# SB_TS_2_08_Final.net
KiCad netlist of a schematic drawn in EAGLE
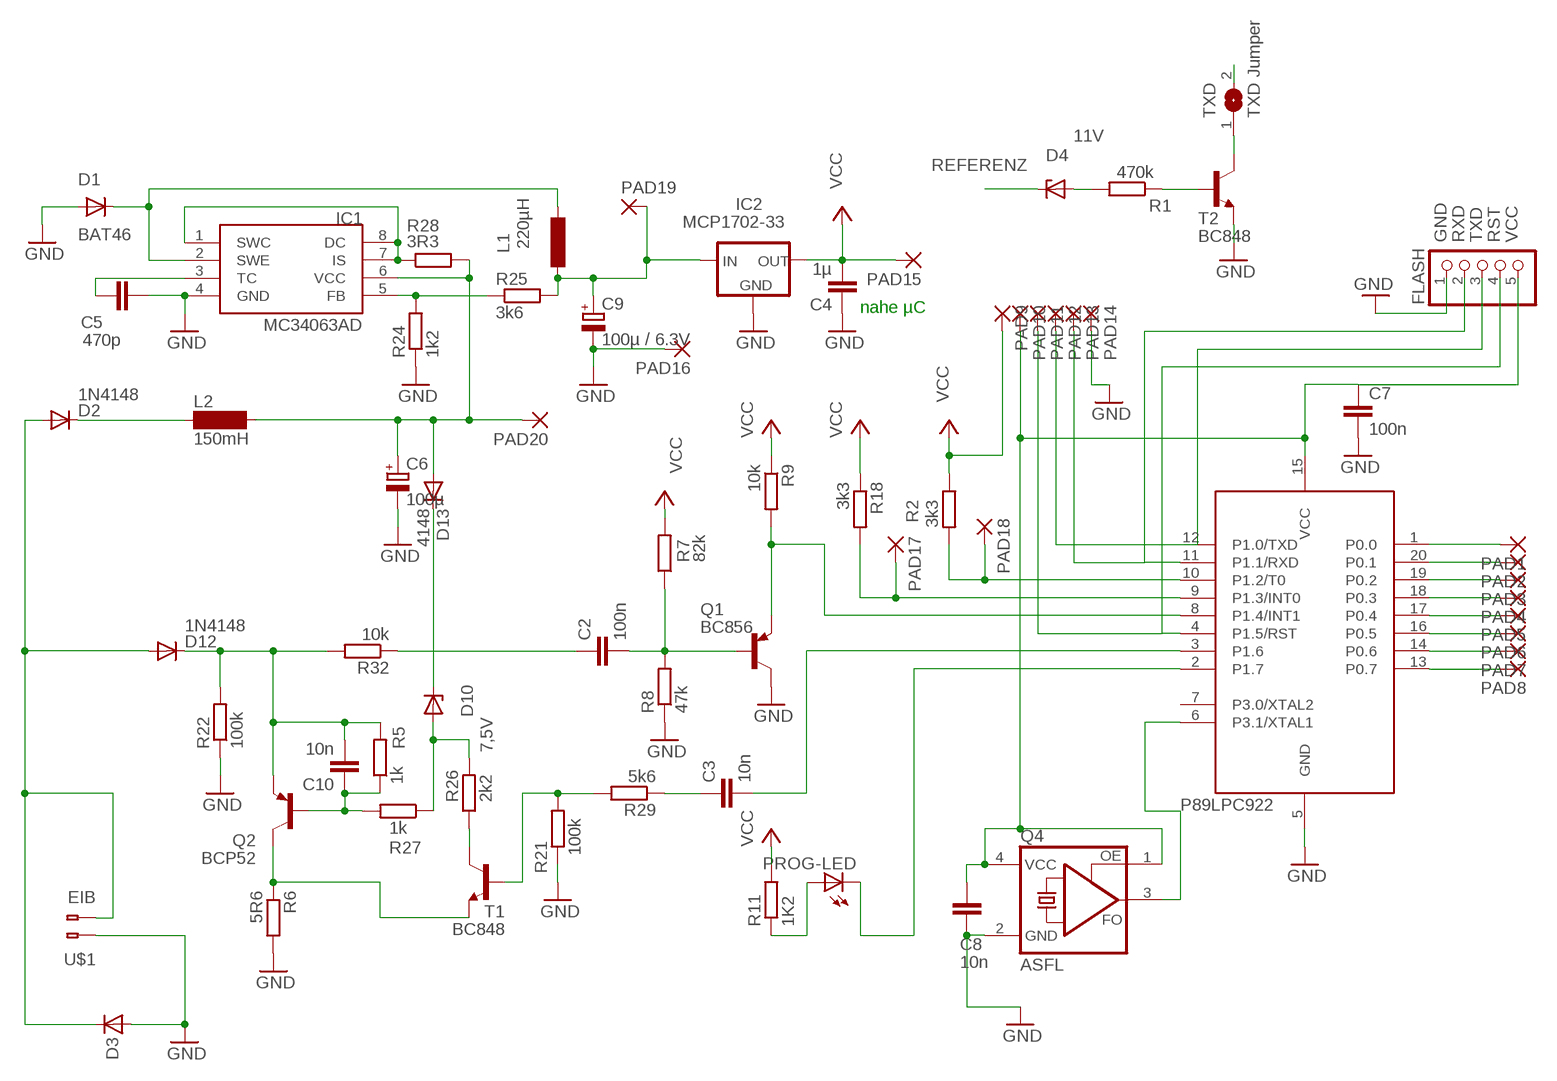
[diagram p0: schematic, sheet 1]

(export (version "E")
  (design (tool "Eeschema 10.0.6"))
  (components
    (comp (ref "C2")
      (value "100n")
      (footprint "eagle-import:C1206")
      (libsource (lib "eagle-import") (part "C-EUC1206"))
    )
    (comp (ref "C3")
      (value "10n")
      (footprint "eagle-import:C1206")
      (libsource (lib "eagle-import") (part "C-EUC1206"))
    )
    (comp (ref "C4")
      (value "1µ")
      (footprint "eagle-import:C1206")
      (libsource (lib "eagle-import") (part "C-EUC1206"))
    )
    (comp (ref "C5")
      (value "470p")
      (footprint "eagle-import:C1206")
      (libsource (lib "eagle-import") (part "C-EUC1206"))
    )
    (comp (ref "C6")
      (value "100µ")
      (footprint "eagle-import:SANYO-OSCON_SMD_C6")
      (libsource (lib "eagle-import") (part "CPOL-EUSANYO_SMD_C6"))
    )
    (comp (ref "C7")
      (value "100n")
      (footprint "eagle-import:C1206")
      (libsource (lib "eagle-import") (part "C-EUC1206"))
    )
    (comp (ref "C8")
      (value "10n")
      (footprint "eagle-import:C1206")
      (libsource (lib "eagle-import") (part "C-EUC1206"))
    )
    (comp (ref "C9")
      (value "100µ / 6.3V")
      (footprint "eagle-import:E2,5-5")
      (libsource (lib "eagle-import") (part "CPOL-EUE2.5-5"))
    )
    (comp (ref "C10")
      (value "10n")
      (footprint "eagle-import:C1206")
      (libsource (lib "eagle-import") (part "C-EUC1206"))
    )
    (comp (ref "D1")
      (value "BAT46")
      (footprint "eagle-import:MINIMELF")
      (libsource (lib "eagle-import") (part "DIODE-MINIMELF"))
    )
    (comp (ref "D2")
      (value "1N4148")
      (footprint "eagle-import:MINIMELF")
      (libsource (lib "eagle-import") (part "DIODE-MINIMELF"))
    )
    (comp (ref "D3")
      (value "SMAJ40AC")
      (footprint "eagle-import:SMB")
      (libsource (lib "eagle-import") (part "D-SMB"))
    )
    (comp (ref "D4")
      (value "11V")
      (footprint "eagle-import:SOD80C")
      (libsource (lib "eagle-import") (part "ZENER-DIODESOD80C"))
    )
    (comp (ref "D10")
      (value "7,5V")
      (footprint "eagle-import:SOD80C")
      (libsource (lib "eagle-import") (part "ZENER-DIODESOD80C"))
    )
    (comp (ref "D12")
      (value "1N4148")
      (footprint "eagle-import:MINIMELF")
      (libsource (lib "eagle-import") (part "DIODE-MINIMELF"))
    )
    (comp (ref "D13")
      (value "4148")
      (footprint "eagle-import:MINIMELF")
      (libsource (lib "eagle-import") (part "DIODE-MINIMELF"))
    )
    (comp (ref "FLASH")
      (value "PINHD-1X5")
      (footprint "eagle-import:1X05")
      (libsource (lib "eagle-import") (part "PINHD-1X5"))
    )
    (comp (ref "IC1")
      (value "MC34063AD")
      (footprint "eagle-import:SOIC8")
      (libsource (lib "eagle-import") (part "MC34063AD"))
    )
    (comp (ref "IC2")
      (value "MCP1702-33")
      (footprint "eagle-import:79LXX")
      (libsource (lib "eagle-import") (part "79LXX"))
    )
    (comp (ref "IC3")
      (value "LPC922FDH")
      (footprint "eagle-import:TSSOP20")
      (libsource (lib "eagle-import") (part "LPC922FDH"))
    )
    (comp (ref "L1")
      (value "220µH")
      (footprint "eagle-import:2200-11.43")
      (libsource (lib "eagle-import") (part "L-EU2200-11.43"))
    )
    (comp (ref "L2")
      (value "150mH")
      (footprint "eagle-import:SD12_1000")
      (libsource (lib "eagle-import") (part "SD12-1000"))
    )
    (comp (ref "PAD1")
      (value "SMD2")
      (footprint "eagle-import:SMD1,27-2,54")
      (libsource (lib "eagle-import") (part "SMD2"))
    )
    (comp (ref "PAD2")
      (value "SMD2")
      (footprint "eagle-import:SMD1,27-2,54")
      (libsource (lib "eagle-import") (part "SMD2"))
    )
    (comp (ref "PAD3")
      (value "SMD2")
      (footprint "eagle-import:SMD1,27-2,54")
      (libsource (lib "eagle-import") (part "SMD2"))
    )
    (comp (ref "PAD4")
      (value "SMD2")
      (footprint "eagle-import:SMD1,27-2,54")
      (libsource (lib "eagle-import") (part "SMD2"))
    )
    (comp (ref "PAD5")
      (value "SMD2")
      (footprint "eagle-import:SMD1,27-2,54")
      (libsource (lib "eagle-import") (part "SMD2"))
    )
    (comp (ref "PAD6")
      (value "SMD2")
      (footprint "eagle-import:SMD1,27-2,54")
      (libsource (lib "eagle-import") (part "SMD2"))
    )
    (comp (ref "PAD7")
      (value "SMD2")
      (footprint "eagle-import:SMD1,27-2,54")
      (libsource (lib "eagle-import") (part "SMD2"))
    )
    (comp (ref "PAD8")
      (value "SMD2")
      (footprint "eagle-import:SMD1,27-2,54")
      (libsource (lib "eagle-import") (part "SMD2"))
    )
    (comp (ref "PAD9")
      (value "SMD2")
      (footprint "eagle-import:SMD1,27-2,54")
      (libsource (lib "eagle-import") (part "SMD2"))
    )
    (comp (ref "PAD10")
      (value "SMD2")
      (footprint "eagle-import:SMD1,27-2,54")
      (libsource (lib "eagle-import") (part "SMD2"))
    )
    (comp (ref "PAD11")
      (value "SMD2")
      (footprint "eagle-import:SMD1,27-2,54")
      (libsource (lib "eagle-import") (part "SMD2"))
    )
    (comp (ref "PAD12")
      (value "SMD2")
      (footprint "eagle-import:SMD1,27-2,54")
      (libsource (lib "eagle-import") (part "SMD2"))
    )
    (comp (ref "PAD13")
      (value "SMD2")
      (footprint "eagle-import:SMD1,27-2,54")
      (libsource (lib "eagle-import") (part "SMD2"))
    )
    (comp (ref "PAD14")
      (value "SMD2")
      (footprint "eagle-import:SMD1,27-2,54")
      (libsource (lib "eagle-import") (part "SMD2"))
    )
    (comp (ref "PAD15")
      (value "SMD2")
      (footprint "eagle-import:SMD1,27-2,54")
      (libsource (lib "eagle-import") (part "SMD2"))
    )
    (comp (ref "PAD16")
      (value "SMD2")
      (footprint "eagle-import:SMD1,27-2,54")
      (libsource (lib "eagle-import") (part "SMD2"))
    )
    (comp (ref "PAD17")
      (value "SMD2")
      (footprint "eagle-import:SMD1,27-2,54")
      (libsource (lib "eagle-import") (part "SMD2"))
    )
    (comp (ref "PAD18")
      (value "SMD2")
      (footprint "eagle-import:SMD1,27-2,54")
      (libsource (lib "eagle-import") (part "SMD2"))
    )
    (comp (ref "PAD19")
      (value "SMD2")
      (footprint "eagle-import:SMD1,27-2,54")
      (libsource (lib "eagle-import") (part "SMD2"))
    )
    (comp (ref "PAD20")
      (value "SMD2")
      (footprint "eagle-import:SMD1,27-2,54")
      (libsource (lib "eagle-import") (part "SMD2"))
    )
    (comp (ref "PROG-LED")
      (value "LEDCHIPLED_1206")
      (footprint "eagle-import:CHIPLED_1206")
      (libsource (lib "eagle-import") (part "LEDCHIPLED_1206"))
    )
    (comp (ref "Q1")
      (value "BC856")
      (footprint "eagle-import:SOT23-BEC")
      (libsource (lib "eagle-import") (part "BC856SMDALT1"))
    )
    (comp (ref "Q2")
      (value "BCP52")
      (footprint "eagle-import:SOT223")
      (libsource (lib "eagle-import") (part "FZT753SMD"))
    )
    (comp (ref "Q4")
      (value "ASFL")
      (footprint "eagle-import:ASF")
      (fields (field (name "MPN") "ASFLM1-50.000MHZ-C-T"))
      (libsource (lib "eagle-import") (part "ASFL"))
    )
    (comp (ref "R1")
      (value "470k")
      (footprint "eagle-import:R1206")
      (libsource (lib "eagle-import") (part "R-EU_R1206"))
    )
    (comp (ref "R2")
      (value "3k3")
      (footprint "eagle-import:M1206")
      (libsource (lib "eagle-import") (part "R-EU_M1206"))
    )
    (comp (ref "R5")
      (value "1k")
      (footprint "eagle-import:R1206")
      (libsource (lib "eagle-import") (part "R-EU_R1206"))
    )
    (comp (ref "R6")
      (value "5R6")
      (footprint "eagle-import:R1206")
      (libsource (lib "eagle-import") (part "R-EU_R1206"))
    )
    (comp (ref "R7")
      (value "82k")
      (footprint "eagle-import:R1206")
      (libsource (lib "eagle-import") (part "R-EU_R1206"))
    )
    (comp (ref "R8")
      (value "47k")
      (footprint "eagle-import:M1206")
      (libsource (lib "eagle-import") (part "R-EU_M1206"))
    )
    (comp (ref "R9")
      (value "10k")
      (footprint "eagle-import:R1206")
      (libsource (lib "eagle-import") (part "R-EU_R1206"))
    )
    (comp (ref "R11")
      (value "1K2")
      (footprint "eagle-import:R1206")
      (libsource (lib "eagle-import") (part "R-EU_R1206"))
    )
    (comp (ref "R18")
      (value "3k3")
      (footprint "eagle-import:R1206")
      (libsource (lib "eagle-import") (part "R-EU_R1206"))
    )
    (comp (ref "R21")
      (value "100k")
      (footprint "eagle-import:R1206")
      (libsource (lib "eagle-import") (part "R-EU_R1206"))
    )
    (comp (ref "R22")
      (value "100k")
      (footprint "eagle-import:M1206")
      (libsource (lib "eagle-import") (part "R-EU_M1206"))
    )
    (comp (ref "R24")
      (value "1k2")
      (footprint "eagle-import:R1206")
      (libsource (lib "eagle-import") (part "R-EU_R1206"))
    )
    (comp (ref "R25")
      (value "3k6")
      (footprint "eagle-import:M1206")
      (libsource (lib "eagle-import") (part "R-EU_M1206"))
    )
    (comp (ref "R26")
      (value "2k2")
      (footprint "eagle-import:M1206")
      (libsource (lib "eagle-import") (part "R-EU_M1206"))
    )
    (comp (ref "R27")
      (value "1k")
      (footprint "eagle-import:R1206")
      (libsource (lib "eagle-import") (part "R-EU_R1206"))
    )
    (comp (ref "R28")
      (value "3R3")
      (footprint "eagle-import:M1206")
      (libsource (lib "eagle-import") (part "R-EU_M1206"))
    )
    (comp (ref "R29")
      (value "5k6")
      (footprint "eagle-import:R1206")
      (libsource (lib "eagle-import") (part "R-EU_R1206"))
    )
    (comp (ref "R32")
      (value "10k")
      (footprint "eagle-import:R1206")
      (libsource (lib "eagle-import") (part "R-EU_R1206"))
    )
    (comp (ref "T1")
      (value "BC848")
      (footprint "eagle-import:SOT23")
      (libsource (lib "eagle-import") (part "BC848"))
    )
    (comp (ref "T2")
      (value "BC848")
      (footprint "eagle-import:SOT23")
      (libsource (lib "eagle-import") (part "BC848"))
    )
    (comp (ref "TXD")
      (value "TXD Jumper")
      (footprint "eagle-import:SJ")
      (libsource (lib "eagle-import") (part "SJ"))
    )
    (comp (ref "U$1")
      (value "EIB")
      (footprint "eagle-import:BUSKLEMME243-724")
      (libsource (lib "eagle-import") (part "EIB"))
    )
  )
  (nets
    (net (code "1") (name "/REFERENZ") (class "Default")
      (node (ref "D10") (pin "A") (pinfunction "A_A") (pintype "passive"))
      (node (ref "D4") (pin "C") (pinfunction "C_C") (pintype "passive"))
      (node (ref "R26") (pin "2") (pinfunction "2_2") (pintype "passive"))
      (node (ref "R27") (pin "1") (pinfunction "1_1") (pintype "passive"))
    )
    (net (code "2") (name "/TXD") (class "Default")
      (node (ref "FLASH") (pin "3") (pinfunction "3_3") (pintype "passive"))
      (node (ref "IC3") (pin "12") (pinfunction "P1.0/TXD_12") (pintype "bidirectional"))
      (node (ref "PAD12") (pin "1") (pinfunction "P_1") (pintype "passive"))
      (node (ref "T2") (pin "3") (pinfunction "C_3") (pintype "passive"))
      (node (ref "TXD") (pin "1") (pinfunction "1_1") (pintype "passive"))
      (node (ref "TXD") (pin "2") (pinfunction "2_2") (pintype "passive"))
    )
    (net (code "3") (name "GND") (class "Default")
      (node (ref "C4") (pin "1") (pinfunction "1_1") (pintype "passive"))
      (node (ref "C5") (pin "2") (pinfunction "2_2") (pintype "passive"))
      (node (ref "C6") (pin "-") (pinfunction "-_-") (pintype "passive"))
      (node (ref "C7") (pin "2") (pinfunction "2_2") (pintype "passive"))
      (node (ref "C8") (pin "2") (pinfunction "2_2") (pintype "passive"))
      (node (ref "C9") (pin "-") (pinfunction "-_-") (pintype "passive"))
      (node (ref "D1") (pin "A") (pinfunction "A_A") (pintype "passive"))
      (node (ref "D3") (pin "2") (pinfunction "A_2") (pintype "passive"))
      (node (ref "FLASH") (pin "1") (pinfunction "1_1") (pintype "passive"))
      (node (ref "IC1") (pin "4") (pinfunction "GND_4") (pintype "passive"))
      (node (ref "IC2") (pin "GND") (pinfunction "GND_GND") (pintype "input"))
      (node (ref "IC3") (pin "5") (pinfunction "GND_5") (pintype "bidirectional"))
      (node (ref "PAD14") (pin "1") (pinfunction "P_1") (pintype "passive"))
      (node (ref "PAD16") (pin "1") (pinfunction "P_1") (pintype "passive"))
      (node (ref "Q1") (pin "C") (pinfunction "C_C") (pintype "passive"))
      (node (ref "Q4") (pin "2") (pinfunction "GND_2") (pintype "power_in"))
      (node (ref "R21") (pin "1") (pinfunction "1_1") (pintype "passive"))
      (node (ref "R22") (pin "1") (pinfunction "1_1") (pintype "passive"))
      (node (ref "R24") (pin "1") (pinfunction "1_1") (pintype "passive"))
      (node (ref "R6") (pin "2") (pinfunction "2_2") (pintype "passive"))
      (node (ref "R8") (pin "1") (pinfunction "1_1") (pintype "passive"))
      (node (ref "T2") (pin "2") (pinfunction "E_2") (pintype "passive"))
      (node (ref "U$1") (pin "1") (pinfunction "B-1_1") (pintype "passive"))
    )
    (net (code "4") (name "Net-(C2-Pad1)") (class "Default")
      (node (ref "C2") (pin "1") (pinfunction "1_1") (pintype "passive"))
      (node (ref "R32") (pin "1") (pinfunction "1_1") (pintype "passive"))
    )
    (net (code "5") (name "Net-(C2-Pad2)") (class "Default")
      (node (ref "C2") (pin "2") (pinfunction "2_2") (pintype "passive"))
      (node (ref "Q1") (pin "B") (pinfunction "B_B") (pintype "passive"))
      (node (ref "R7") (pin "1") (pinfunction "1_1") (pintype "passive"))
      (node (ref "R8") (pin "2") (pinfunction "2_2") (pintype "passive"))
    )
    (net (code "6") (name "Net-(C3-Pad1)") (class "Default")
      (node (ref "C3") (pin "1") (pinfunction "1_1") (pintype "passive"))
      (node (ref "R29") (pin "1") (pinfunction "1_1") (pintype "passive"))
    )
    (net (code "7") (name "Net-(D2-PadC)") (class "Default")
      (node (ref "D2") (pin "C") (pinfunction "C_C") (pintype "passive"))
      (node (ref "L2") (pin "1") (pinfunction "1_1") (pintype "passive"))
    )
    (net (code "8") (name "Net-(D3-C)") (class "Default")
      (node (ref "D12") (pin "A") (pinfunction "A_A") (pintype "passive"))
      (node (ref "D2") (pin "A") (pinfunction "A_A") (pintype "passive"))
      (node (ref "D3") (pin "1") (pinfunction "C_1") (pintype "passive"))
      (node (ref "U$1") (pin "2") (pinfunction "B-2_2") (pintype "passive"))
    )
    (net (code "9") (name "Net-(D4-PadA)") (class "Default")
      (node (ref "D4") (pin "A") (pinfunction "A_A") (pintype "passive"))
      (node (ref "R1") (pin "2") (pinfunction "2_2") (pintype "passive"))
    )
    (net (code "10") (name "Net-(D10-PadC)") (class "Default")
      (node (ref "D10") (pin "C") (pinfunction "C_C") (pintype "passive"))
      (node (ref "D13") (pin "C") (pinfunction "C_C") (pintype "passive"))
    )
    (net (code "11") (name "Net-(IC1-DC)") (class "Default")
      (node (ref "IC1") (pin "1") (pinfunction "SWC_1") (pintype "passive"))
      (node (ref "IC1") (pin "7") (pinfunction "IS_7") (pintype "passive"))
      (node (ref "IC1") (pin "8") (pinfunction "DC_8") (pintype "passive"))
      (node (ref "R28") (pin "1") (pinfunction "1_1") (pintype "passive"))
    )
    (net (code "12") (name "Net-(IC1-FB)") (class "Default")
      (node (ref "IC1") (pin "5") (pinfunction "FB_5") (pintype "passive"))
      (node (ref "R24") (pin "2") (pinfunction "2_2") (pintype "passive"))
      (node (ref "R25") (pin "1") (pinfunction "1_1") (pintype "passive"))
    )
    (net (code "13") (name "Net-(IC1-SWE)") (class "Default")
      (node (ref "D1") (pin "C") (pinfunction "C_C") (pintype "passive"))
      (node (ref "IC1") (pin "2") (pinfunction "SWE_2") (pintype "passive"))
      (node (ref "L1") (pin "2") (pinfunction "2_2") (pintype "passive"))
    )
    (net (code "14") (name "Net-(IC1-TC)") (class "Default")
      (node (ref "C5") (pin "1") (pinfunction "1_1") (pintype "passive"))
      (node (ref "IC1") (pin "3") (pinfunction "TC_3") (pintype "passive"))
    )
    (net (code "15") (name "Net-(IC1-VCC)") (class "Default")
      (node (ref "C6") (pin "+") (pinfunction "+_+") (pintype "passive"))
      (node (ref "D13") (pin "A") (pinfunction "A_A") (pintype "passive"))
      (node (ref "IC1") (pin "6") (pinfunction "VCC_6") (pintype "passive"))
      (node (ref "L2") (pin "2") (pinfunction "2_2") (pintype "passive"))
      (node (ref "PAD20") (pin "1") (pinfunction "P_1") (pintype "passive"))
      (node (ref "R28") (pin "2") (pinfunction "2_2") (pintype "passive"))
    )
    (net (code "16") (name "Net-(IC3-P0.0)") (class "Default")
      (node (ref "IC3") (pin "1") (pinfunction "P0.0_1") (pintype "bidirectional"))
      (node (ref "PAD1") (pin "1") (pinfunction "P_1") (pintype "passive"))
    )
    (net (code "17") (name "Net-(IC3-P0.1)") (class "Default")
      (node (ref "IC3") (pin "20") (pinfunction "P0.1_20") (pintype "bidirectional"))
      (node (ref "PAD2") (pin "1") (pinfunction "P_1") (pintype "passive"))
    )
    (net (code "18") (name "Net-(IC3-P0.2)") (class "Default")
      (node (ref "IC3") (pin "19") (pinfunction "P0.2_19") (pintype "bidirectional"))
      (node (ref "PAD3") (pin "1") (pinfunction "P_1") (pintype "passive"))
    )
    (net (code "19") (name "Net-(IC3-P0.3)") (class "Default")
      (node (ref "IC3") (pin "18") (pinfunction "P0.3_18") (pintype "bidirectional"))
      (node (ref "PAD4") (pin "1") (pinfunction "P_1") (pintype "passive"))
    )
    (net (code "20") (name "Net-(IC3-P0.4)") (class "Default")
      (node (ref "IC3") (pin "17") (pinfunction "P0.4_17") (pintype "bidirectional"))
      (node (ref "PAD5") (pin "1") (pinfunction "P_1") (pintype "passive"))
    )
    (net (code "21") (name "Net-(IC3-P0.5)") (class "Default")
      (node (ref "IC3") (pin "16") (pinfunction "P0.5_16") (pintype "bidirectional"))
      (node (ref "PAD6") (pin "1") (pinfunction "P_1") (pintype "passive"))
    )
    (net (code "22") (name "Net-(IC3-P0.6)") (class "Default")
      (node (ref "IC3") (pin "14") (pinfunction "P0.6_14") (pintype "bidirectional"))
      (node (ref "PAD7") (pin "1") (pinfunction "P_1") (pintype "passive"))
    )
    (net (code "23") (name "Net-(IC3-P0.7)") (class "Default")
      (node (ref "IC3") (pin "13") (pinfunction "P0.7_13") (pintype "bidirectional"))
      (node (ref "PAD8") (pin "1") (pinfunction "P_1") (pintype "passive"))
    )
    (net (code "24") (name "Net-(IC3-P1.1{slash}RXD)") (class "Default")
      (node (ref "FLASH") (pin "2") (pinfunction "2_2") (pintype "passive"))
      (node (ref "IC3") (pin "11") (pinfunction "P1.1/RXD_11") (pintype "bidirectional"))
      (node (ref "PAD13") (pin "1") (pinfunction "P_1") (pintype "passive"))
    )
    (net (code "25") (name "Net-(IC3-P1.2{slash}T0)") (class "Default")
      (node (ref "IC3") (pin "10") (pinfunction "P1.2/T0_10") (pintype "bidirectional"))
      (node (ref "PAD18") (pin "1") (pinfunction "P_1") (pintype "passive"))
      (node (ref "R2") (pin "2") (pinfunction "2_2") (pintype "passive"))
    )
    (net (code "26") (name "Net-(IC3-P1.3{slash}INT0)") (class "Default")
      (node (ref "IC3") (pin "9") (pinfunction "P1.3/INT0_9") (pintype "bidirectional"))
      (node (ref "PAD17") (pin "1") (pinfunction "P_1") (pintype "passive"))
      (node (ref "R18") (pin "2") (pinfunction "2_2") (pintype "passive"))
    )
    (net (code "27") (name "Net-(IC3-P1.4{slash}INT1)") (class "Default")
      (node (ref "IC3") (pin "8") (pinfunction "P1.4/INT1_8") (pintype "bidirectional"))
      (node (ref "Q1") (pin "E") (pinfunction "E_E") (pintype "passive"))
      (node (ref "R9") (pin "2") (pinfunction "2_2") (pintype "passive"))
    )
    (net (code "28") (name "Net-(IC3-P1.5{slash}RST)") (class "Default")
      (node (ref "FLASH") (pin "4") (pinfunction "4_4") (pintype "passive"))
      (node (ref "IC3") (pin "4") (pinfunction "P1.5/RST_4") (pintype "bidirectional"))
      (node (ref "PAD11") (pin "1") (pinfunction "P_1") (pintype "passive"))
    )
    (net (code "29") (name "Net-(IC3-P1.6)") (class "Default")
      (node (ref "C3") (pin "2") (pinfunction "2_2") (pintype "passive"))
      (node (ref "IC3") (pin "3") (pinfunction "P1.6_3") (pintype "bidirectional"))
    )
    (net (code "30") (name "Net-(IC3-P1.7)") (class "Default")
      (node (ref "IC3") (pin "2") (pinfunction "P1.7_2") (pintype "bidirectional"))
      (node (ref "PROG-LED") (pin "C") (pinfunction "C_C") (pintype "passive"))
    )
    (net (code "31") (name "Net-(IC3-P3.1{slash}XTAL1)") (class "Default")
      (node (ref "IC3") (pin "6") (pinfunction "P3.1/XTAL1_6") (pintype "bidirectional"))
      (node (ref "Q4") (pin "3") (pinfunction "FO_3") (pintype "output"))
    )
    (net (code "32") (name "Net-(IC3-VCC)") (class "Default")
      (node (ref "C7") (pin "1") (pinfunction "1_1") (pintype "passive"))
      (node (ref "C8") (pin "1") (pinfunction "1_1") (pintype "passive"))
      (node (ref "FLASH") (pin "5") (pinfunction "5_5") (pintype "passive"))
      (node (ref "IC3") (pin "15") (pinfunction "VCC_15") (pintype "bidirectional"))
      (node (ref "PAD10") (pin "1") (pinfunction "P_1") (pintype "passive"))
      (node (ref "Q4") (pin "1") (pinfunction "OE_1") (pintype "input"))
      (node (ref "Q4") (pin "4") (pinfunction "VCC_4") (pintype "power_in"))
    )
    (net (code "33") (name "Net-(PAD19-P)") (class "Default")
      (node (ref "C9") (pin "+") (pinfunction "+_+") (pintype "passive"))
      (node (ref "IC2") (pin "IN") (pinfunction "IN_IN") (pintype "input"))
      (node (ref "L1") (pin "1") (pinfunction "1_1") (pintype "passive"))
      (node (ref "PAD19") (pin "1") (pinfunction "P_1") (pintype "passive"))
      (node (ref "R25") (pin "2") (pinfunction "2_2") (pintype "passive"))
    )
    (net (code "34") (name "Net-(PROG-LED-PadA)") (class "Default")
      (node (ref "PROG-LED") (pin "A") (pinfunction "A_A") (pintype "passive"))
      (node (ref "R11") (pin "1") (pinfunction "1_1") (pintype "passive"))
    )
    (net (code "35") (name "Net-(Q2-B)") (class "Default")
      (node (ref "C10") (pin "1") (pinfunction "1_1") (pintype "passive"))
      (node (ref "Q2") (pin "1") (pinfunction "B_1") (pintype "passive"))
      (node (ref "R27") (pin "2") (pinfunction "2_2") (pintype "passive"))
      (node (ref "R5") (pin "1") (pinfunction "1_1") (pintype "passive"))
    )
    (net (code "36") (name "Net-(Q2-E)") (class "Default")
      (node (ref "C10") (pin "2") (pinfunction "2_2") (pintype "passive"))
      (node (ref "D12") (pin "C") (pinfunction "C_C") (pintype "passive"))
      (node (ref "Q2") (pin "3") (pinfunction "E_3") (pintype "passive"))
      (node (ref "R22") (pin "2") (pinfunction "2_2") (pintype "passive"))
      (node (ref "R32") (pin "2") (pinfunction "2_2") (pintype "passive"))
      (node (ref "R5") (pin "2") (pinfunction "2_2") (pintype "passive"))
    )
    (net (code "37") (name "Net-(T1-B)") (class "Default")
      (node (ref "R21") (pin "2") (pinfunction "2_2") (pintype "passive"))
      (node (ref "R29") (pin "2") (pinfunction "2_2") (pintype "passive"))
      (node (ref "T1") (pin "1") (pinfunction "B_1") (pintype "passive"))
    )
    (net (code "38") (name "Net-(T1-C)") (class "Default")
      (node (ref "R26") (pin "1") (pinfunction "1_1") (pintype "passive"))
      (node (ref "T1") (pin "3") (pinfunction "C_3") (pintype "passive"))
    )
    (net (code "39") (name "Net-(T1-E)") (class "Default")
      (node (ref "Q2") (pin "2") (pinfunction "C_2") (pintype "passive"))
      (node (ref "Q2") (pin "4") (pinfunction "C_4") (pintype "passive"))
      (node (ref "R6") (pin "1") (pinfunction "1_1") (pintype "passive"))
      (node (ref "T1") (pin "2") (pinfunction "E_2") (pintype "passive"))
    )
    (net (code "40") (name "Net-(T2-B)") (class "Default")
      (node (ref "R1") (pin "1") (pinfunction "1_1") (pintype "passive"))
      (node (ref "T2") (pin "1") (pinfunction "B_1") (pintype "passive"))
    )
    (net (code "41") (name "VCC") (class "Default")
      (node (ref "C4") (pin "2") (pinfunction "2_2") (pintype "passive"))
      (node (ref "IC2") (pin "OUT") (pinfunction "OUT_OUT") (pintype "passive"))
      (node (ref "PAD15") (pin "1") (pinfunction "P_1") (pintype "passive"))
      (node (ref "PAD9") (pin "1") (pinfunction "P_1") (pintype "passive"))
      (node (ref "R11") (pin "2") (pinfunction "2_2") (pintype "passive"))
      (node (ref "R18") (pin "1") (pinfunction "1_1") (pintype "passive"))
      (node (ref "R2") (pin "1") (pinfunction "1_1") (pintype "passive"))
      (node (ref "R7") (pin "2") (pinfunction "2_2") (pintype "passive"))
      (node (ref "R9") (pin "1") (pinfunction "1_1") (pintype "passive"))
    )
    (net (code "42") (name "unconnected-(IC3-P3.0{slash}XTAL2-Pad7)") (class "Default")
      (node (ref "IC3") (pin "7") (pinfunction "P3.0/XTAL2_7") (pintype "bidirectional"))
    )
  )
)
